# Micro_RC_Transmitter_1_1.net
KiCad netlist of a schematic drawn in EAGLE
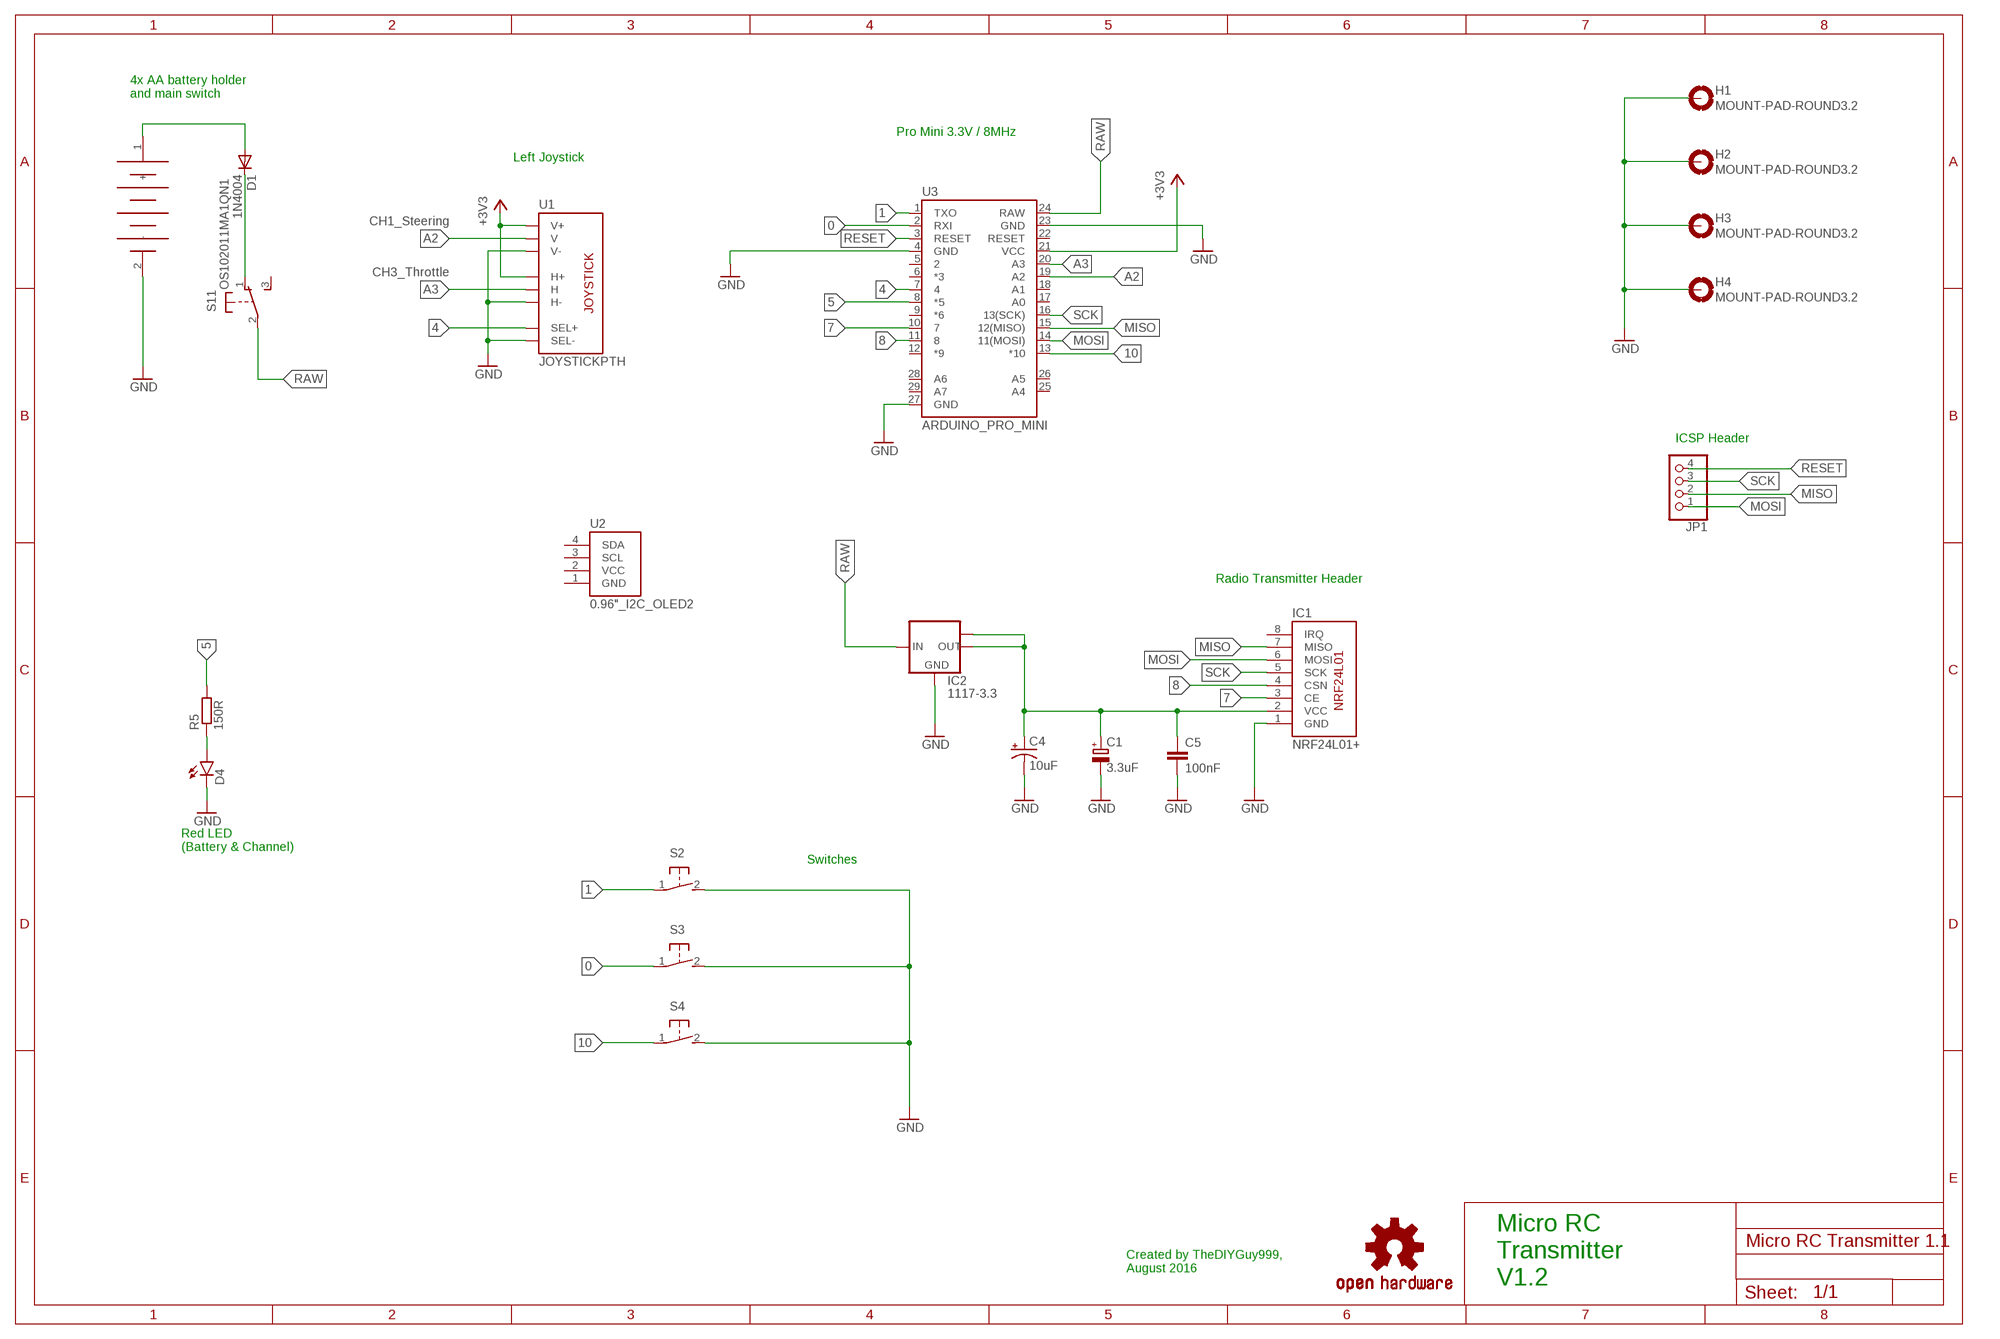
[diagram p0: schematic, sheet 1]

(export (version "E")
  (design (tool "Eeschema 10.0.6"))
  (components
    (comp (ref "C1")
      (value "3.3uF")
      (footprint "eagle-import:B45181A")
      (libsource (lib "eagle-import") (part "CPOL-EUB45181A"))
    )
    (comp (ref "C4")
      (value "10uF")
      (footprint "eagle-import:EIA3216")
      (libsource (lib "eagle-import") (part "10UF-16V-10%(TANT)"))
    )
    (comp (ref "C5")
      (value "100nF")
      (footprint "eagle-import:C0805")
      (libsource (lib "eagle-import") (part "C-EUC0805"))
    )
    (comp (ref "D1")
      (value "1N4004")
      (footprint "eagle-import:DO-214AC")
      (libsource (lib "eagle-import") (part "DIODE-DO-214AC"))
    )
    (comp (ref "D4")
      (value "LED3MM")
      (footprint "eagle-import:LED3MM")
      (libsource (lib "eagle-import") (part "LED3MM"))
    )
    (comp (ref "G1")
      (value "4X_AA_BATTERY_HOLDER")
      (footprint "eagle-import:4X_AA_BATTERY_HOLDER")
      (libsource (lib "eagle-import") (part "4X_AA_BATTERY_HOLDER"))
    )
    (comp (ref "H1")
      (value "MOUNT-PAD-ROUND3.2")
      (footprint "eagle-import:3,2-PAD")
      (libsource (lib "eagle-import") (part "MOUNT-PAD-ROUND3.2"))
    )
    (comp (ref "H2")
      (value "MOUNT-PAD-ROUND3.2")
      (footprint "eagle-import:3,2-PAD")
      (libsource (lib "eagle-import") (part "MOUNT-PAD-ROUND3.2"))
    )
    (comp (ref "H3")
      (value "MOUNT-PAD-ROUND3.2")
      (footprint "eagle-import:3,2-PAD")
      (libsource (lib "eagle-import") (part "MOUNT-PAD-ROUND3.2"))
    )
    (comp (ref "H4")
      (value "MOUNT-PAD-ROUND3.2")
      (footprint "eagle-import:3,2-PAD")
      (libsource (lib "eagle-import") (part "MOUNT-PAD-ROUND3.2"))
    )
    (comp (ref "IC1")
      (value "NRF24L01+")
      (footprint "eagle-import:NRF24L01")
      (libsource (lib "eagle-import") (part "NRF24L01"))
    )
    (comp (ref "IC2")
      (value "1117-3.3")
      (footprint "eagle-import:SOT223")
      (libsource (lib "eagle-import") (part "LM1117MPX-3.3"))
    )
    (comp (ref "JP1")
      (value "PINHD-1X4")
      (footprint "eagle-import:1X04")
      (libsource (lib "eagle-import") (part "PINHD-1X4"))
    )
    (comp (ref "LOGO1")
      (value "OSHW-LOGOM")
      (footprint "eagle-import:OSHW-LOGO-M")
      (libsource (lib "eagle-import") (part "OSHW-LOGOM"))
    )
    (comp (ref "R5")
      (value "150R")
      (footprint "eagle-import:R0805")
      (libsource (lib "eagle-import") (part "R-EU_R0805"))
    )
    (comp (ref "S1")
      (value "OS102011MA1QN1")
      (footprint "eagle-import:OS102011MA1QN1")
      (libsource (lib "eagle-import") (part "OS102011MA1QN1"))
    )
    (comp (ref "S2")
      (value "31-XX")
      (footprint "eagle-import:B3F-31XX")
      (fields (field (name "MPN") "B3F-3100"))
      (libsource (lib "eagle-import") (part "31-XX"))
    )
    (comp (ref "S3")
      (value "31-XX")
      (footprint "eagle-import:B3F-31XX")
      (fields (field (name "MPN") "B3F-3100"))
      (libsource (lib "eagle-import") (part "31-XX"))
    )
    (comp (ref "S4")
      (value "31-XX")
      (footprint "eagle-import:B3F-31XX")
      (fields (field (name "MPN") "B3F-3100"))
      (libsource (lib "eagle-import") (part "31-XX"))
    )
    (comp (ref "U1")
      (value "JOYSTICKPTH")
      (footprint "eagle-import:JOYSTICK")
      (libsource (lib "eagle-import") (part "JOYSTICKPTH"))
    )
    (comp (ref "U2")
      (value "0.96\"_I2C_OLED2")
      (footprint "eagle-import:0.96__I2C_OLED_2")
      (libsource (lib "eagle-import") (part "0.96{dblquote}_I2C_OLED2"))
    )
    (comp (ref "U3")
      (value "ARDUINO_PRO_MINI")
      (footprint "eagle-import:ARDUINO_PRO_MINI")
      (libsource (lib "eagle-import") (part "ARDUINO_PRO_MINI"))
    )
  )
  (nets
    (net (code "1") (name "+3V3") (class "Default")
      (node (ref "U1") (pin "H1") (pinfunction "H+_H1") (pintype "bidirectional"))
      (node (ref "U1") (pin "V1") (pinfunction "V+_V1") (pintype "bidirectional"))
      (node (ref "U3") (pin "21") (pinfunction "VCC_21") (pintype "bidirectional"))
    )
    (net (code "2") (name "0") (class "Default")
      (node (ref "S3") (pin "1") (pinfunction "P_1") (pintype "passive"))
      (node (ref "U3") (pin "2") (pinfunction "RXI_2") (pintype "bidirectional"))
    )
    (net (code "3") (name "1") (class "Default")
      (node (ref "S2") (pin "1") (pinfunction "P_1") (pintype "passive"))
      (node (ref "U3") (pin "1") (pinfunction "TXO_1") (pintype "bidirectional"))
    )
    (net (code "4") (name "4") (class "Default")
      (node (ref "U1") (pin "B1A") (pinfunction "SEL+_B1A") (pintype "bidirectional"))
      (node (ref "U3") (pin "7") (pinfunction "4_7") (pintype "bidirectional"))
    )
    (net (code "5") (name "5") (class "Default")
      (node (ref "R5") (pin "2") (pinfunction "2_2") (pintype "passive"))
      (node (ref "U3") (pin "8") (pinfunction "*5_8") (pintype "bidirectional"))
    )
    (net (code "6") (name "7") (class "Default")
      (node (ref "IC1") (pin "3") (pinfunction "CE_3") (pintype "bidirectional"))
      (node (ref "U3") (pin "10") (pinfunction "7_10") (pintype "bidirectional"))
    )
    (net (code "7") (name "8") (class "Default")
      (node (ref "IC1") (pin "4") (pinfunction "CSN_4") (pintype "bidirectional"))
      (node (ref "U3") (pin "11") (pinfunction "8_11") (pintype "bidirectional"))
    )
    (net (code "8") (name "10") (class "Default")
      (node (ref "S4") (pin "1") (pinfunction "P_1") (pintype "passive"))
      (node (ref "U3") (pin "13") (pinfunction "*10_13") (pintype "bidirectional"))
    )
    (net (code "9") (name "A2") (class "Default")
      (node (ref "U1") (pin "V2") (pinfunction "V_V2") (pintype "bidirectional"))
      (node (ref "U3") (pin "19") (pinfunction "A2_19") (pintype "bidirectional"))
    )
    (net (code "10") (name "A3") (class "Default")
      (node (ref "U1") (pin "H2") (pinfunction "H_H2") (pintype "bidirectional"))
      (node (ref "U3") (pin "20") (pinfunction "A3_20") (pintype "bidirectional"))
    )
    (net (code "11") (name "GND") (class "Default")
      (node (ref "C1") (pin "-") (pinfunction "-_-") (pintype "passive"))
      (node (ref "C4") (pin "C") (pinfunction "-_C") (pintype "passive"))
      (node (ref "C5") (pin "2") (pinfunction "2_2") (pintype "passive"))
      (node (ref "D4") (pin "K") (pinfunction "C_K") (pintype "passive"))
      (node (ref "G1") (pin "2") (pinfunction "-_2") (pintype "bidirectional"))
      (node (ref "H1") (pin "B3,2") (pinfunction "MOUNT_B3,2") (pintype "passive"))
      (node (ref "H2") (pin "B3,2") (pinfunction "MOUNT_B3,2") (pintype "passive"))
      (node (ref "H3") (pin "B3,2") (pinfunction "MOUNT_B3,2") (pintype "passive"))
      (node (ref "H4") (pin "B3,2") (pinfunction "MOUNT_B3,2") (pintype "passive"))
      (node (ref "IC1") (pin "1") (pinfunction "GND_1") (pintype "bidirectional"))
      (node (ref "IC2") (pin "1") (pinfunction "GND_1") (pintype "input"))
      (node (ref "S2") (pin "2") (pinfunction "S_2") (pintype "passive"))
      (node (ref "S3") (pin "2") (pinfunction "S_2") (pintype "passive"))
      (node (ref "S4") (pin "2") (pinfunction "S_2") (pintype "passive"))
      (node (ref "U1") (pin "B2A") (pinfunction "SEL-_B2A") (pintype "bidirectional"))
      (node (ref "U1") (pin "H3") (pinfunction "H-_H3") (pintype "bidirectional"))
      (node (ref "U1") (pin "V3") (pinfunction "V-_V3") (pintype "bidirectional"))
      (node (ref "U3") (pin "23") (pinfunction "GND_23") (pintype "bidirectional"))
      (node (ref "U3") (pin "27") (pinfunction "GND_27") (pintype "bidirectional"))
      (node (ref "U3") (pin "4") (pinfunction "GND_4") (pintype "bidirectional"))
    )
    (net (code "12") (name "MISO") (class "Default")
      (node (ref "IC1") (pin "7") (pinfunction "MISO_7") (pintype "bidirectional"))
      (node (ref "JP1") (pin "2") (pinfunction "2_2") (pintype "passive"))
      (node (ref "U3") (pin "15") (pinfunction "12(MISO)_15") (pintype "bidirectional"))
    )
    (net (code "13") (name "MOSI") (class "Default")
      (node (ref "IC1") (pin "6") (pinfunction "MOSI_6") (pintype "bidirectional"))
      (node (ref "JP1") (pin "1") (pinfunction "1_1") (pintype "passive"))
      (node (ref "U3") (pin "14") (pinfunction "11(MOSI)_14") (pintype "bidirectional"))
    )
    (net (code "14") (name "Net-(C4-+)") (class "Default")
      (node (ref "C1") (pin "+") (pinfunction "+_+") (pintype "passive"))
      (node (ref "C4") (pin "A") (pinfunction "+_A") (pintype "passive"))
      (node (ref "C5") (pin "1") (pinfunction "1_1") (pintype "passive"))
      (node (ref "IC1") (pin "2") (pinfunction "VCC_2") (pintype "bidirectional"))
      (node (ref "IC2") (pin "2") (pinfunction "OUT_2") (pintype "passive"))
      (node (ref "IC2") (pin "TAB") (pinfunction "OUT1_TAB") (pintype "passive"))
    )
    (net (code "15") (name "Net-(D4-PadA)") (class "Default")
      (node (ref "D4") (pin "A") (pinfunction "A_A") (pintype "passive"))
      (node (ref "R5") (pin "1") (pinfunction "1_1") (pintype "passive"))
    )
    (net (code "16") (name "Net-(G1-+)") (class "Default")
      (node (ref "D1") (pin "A") (pinfunction "A_A") (pintype "passive"))
      (node (ref "G1") (pin "1") (pinfunction "+_1") (pintype "bidirectional"))
    )
    (net (code "17") (name "Net-(S1A-O)") (class "Default")
      (node (ref "D1") (pin "C") (pinfunction "C_C") (pintype "passive"))
      (node (ref "S1") (pin "1") (pinfunction "O_1") (pintype "passive"))
    )
    (net (code "18") (name "RAW") (class "Default")
      (node (ref "IC2") (pin "3") (pinfunction "IN_3") (pintype "input"))
      (node (ref "S1") (pin "2") (pinfunction "P_2") (pintype "passive"))
      (node (ref "U3") (pin "24") (pinfunction "RAW_24") (pintype "bidirectional"))
    )
    (net (code "19") (name "RESET") (class "Default")
      (node (ref "JP1") (pin "4") (pinfunction "4_4") (pintype "passive"))
      (node (ref "U3") (pin "3") (pinfunction "RESET_3") (pintype "bidirectional"))
    )
    (net (code "20") (name "SCK") (class "Default")
      (node (ref "IC1") (pin "5") (pinfunction "SCK_5") (pintype "bidirectional"))
      (node (ref "JP1") (pin "3") (pinfunction "3_3") (pintype "passive"))
      (node (ref "U3") (pin "16") (pinfunction "13(SCK)_16") (pintype "bidirectional"))
    )
    (net (code "21") (name "unconnected-(IC1-IRQ-Pad8)") (class "Default")
      (node (ref "IC1") (pin "8") (pinfunction "IRQ_8") (pintype "bidirectional"))
    )
    (net (code "22") (name "unconnected-(S1A-S-Pad3)") (class "Default")
      (node (ref "S1") (pin "3") (pinfunction "S_3") (pintype "passive"))
    )
    (net (code "23") (name "unconnected-(U2-GND-Pad1)") (class "Default")
      (node (ref "U2") (pin "1") (pinfunction "GND_1") (pintype "bidirectional"))
    )
    (net (code "24") (name "unconnected-(U2-SCL-Pad3)") (class "Default")
      (node (ref "U2") (pin "3") (pinfunction "SCL_3") (pintype "bidirectional"))
    )
    (net (code "25") (name "unconnected-(U2-SDA-Pad4)") (class "Default")
      (node (ref "U2") (pin "4") (pinfunction "SDA_4") (pintype "bidirectional"))
    )
    (net (code "26") (name "unconnected-(U2-VCC-Pad2)") (class "Default")
      (node (ref "U2") (pin "2") (pinfunction "VCC_2") (pintype "bidirectional"))
    )
    (net (code "27") (name "unconnected-(U3-*3-Pad6)") (class "Default")
      (node (ref "U3") (pin "6") (pinfunction "*3_6") (pintype "bidirectional"))
    )
    (net (code "28") (name "unconnected-(U3-*6-Pad9)") (class "Default")
      (node (ref "U3") (pin "9") (pinfunction "*6_9") (pintype "bidirectional"))
    )
    (net (code "29") (name "unconnected-(U3-*9-Pad12)") (class "Default")
      (node (ref "U3") (pin "12") (pinfunction "*9_12") (pintype "bidirectional"))
    )
    (net (code "30") (name "unconnected-(U3-2-Pad5)") (class "Default")
      (node (ref "U3") (pin "5") (pinfunction "2_5") (pintype "bidirectional"))
    )
    (net (code "31") (name "unconnected-(U3-A0-Pad17)") (class "Default")
      (node (ref "U3") (pin "17") (pinfunction "A0_17") (pintype "bidirectional"))
    )
    (net (code "32") (name "unconnected-(U3-A1-Pad18)") (class "Default")
      (node (ref "U3") (pin "18") (pinfunction "A1_18") (pintype "bidirectional"))
    )
    (net (code "33") (name "unconnected-(U3-A4-Pad25)") (class "Default")
      (node (ref "U3") (pin "25") (pinfunction "A4_25") (pintype "bidirectional"))
    )
    (net (code "34") (name "unconnected-(U3-A5-Pad26)") (class "Default")
      (node (ref "U3") (pin "26") (pinfunction "A5_26") (pintype "bidirectional"))
    )
    (net (code "35") (name "unconnected-(U3-A6-Pad28)") (class "Default")
      (node (ref "U3") (pin "28") (pinfunction "A6_28") (pintype "bidirectional"))
    )
    (net (code "36") (name "unconnected-(U3-A7-Pad29)") (class "Default")
      (node (ref "U3") (pin "29") (pinfunction "A7_29") (pintype "bidirectional"))
    )
    (net (code "37") (name "unconnected-(U3-RESET-Pad22)") (class "Default")
      (node (ref "U3") (pin "22") (pinfunction "RESET_22") (pintype "bidirectional"))
    )
  )
)
